# AMP_OP.net
KiCad netlist of a schematic drawn in EAGLE
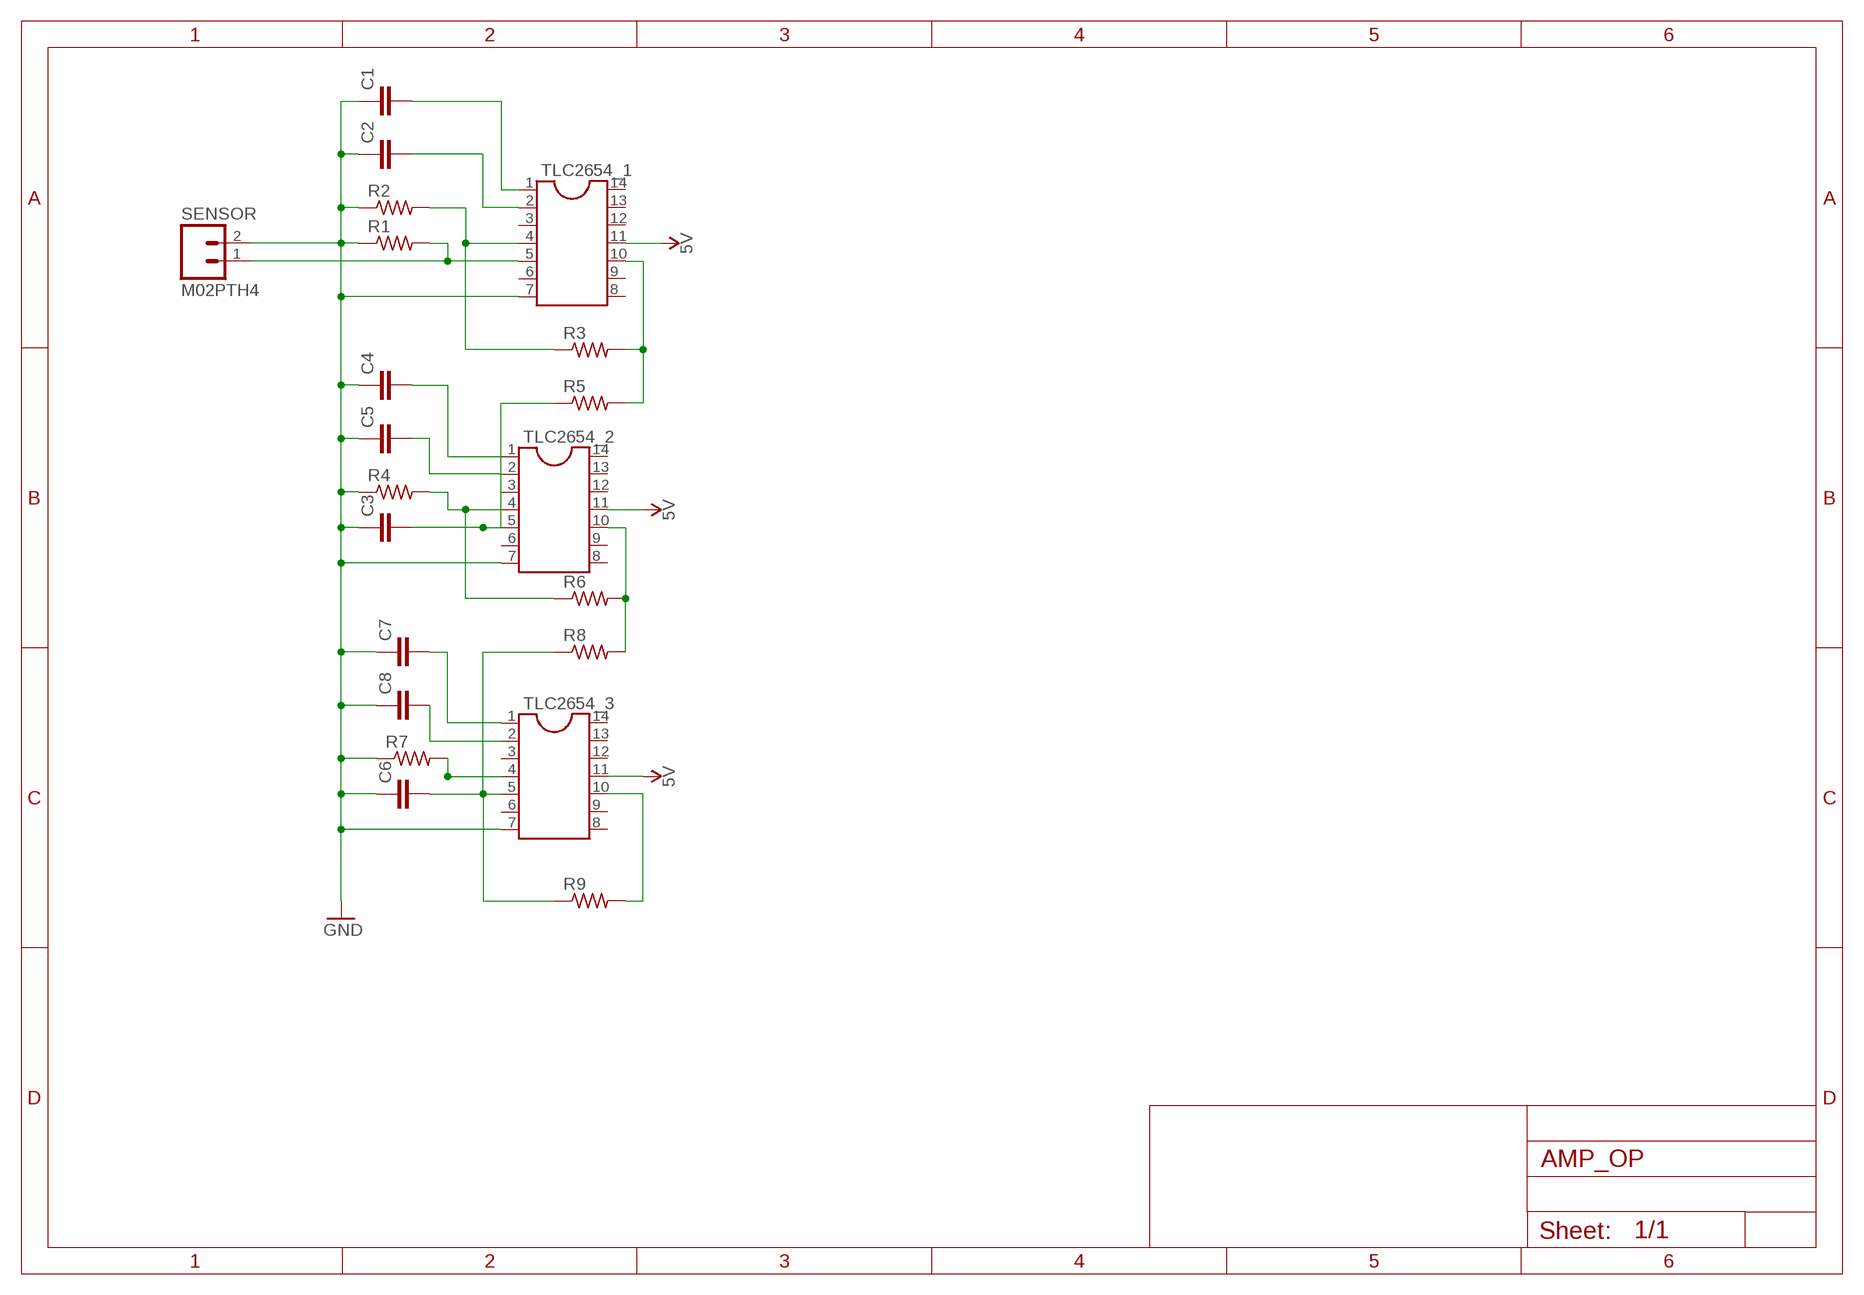
[diagram p0: schematic, sheet 1]

(export (version "E")
  (design (tool "Eeschema 10.0.6"))
  (components
    (comp (ref "C1")
      (value "C5/3.5")
      (footprint "eagle-import:C5B3.5")
      (libsource (lib "eagle-import") (part "C5/3.5"))
    )
    (comp (ref "C2")
      (value "C5/3.5")
      (footprint "eagle-import:C5B3.5")
      (libsource (lib "eagle-import") (part "C5/3.5"))
    )
    (comp (ref "C3")
      (value "C5/3.5")
      (footprint "eagle-import:C5B3.5")
      (libsource (lib "eagle-import") (part "C5/3.5"))
    )
    (comp (ref "C4")
      (value "C5/3.5")
      (footprint "eagle-import:C5B3.5")
      (libsource (lib "eagle-import") (part "C5/3.5"))
    )
    (comp (ref "C5")
      (value "C5/3.5")
      (footprint "eagle-import:C5B3.5")
      (libsource (lib "eagle-import") (part "C5/3.5"))
    )
    (comp (ref "C6")
      (value "C5/3.5")
      (footprint "eagle-import:C5B3.5")
      (libsource (lib "eagle-import") (part "C5/3.5"))
    )
    (comp (ref "C7")
      (value "C5/3.5")
      (footprint "eagle-import:C5B3.5")
      (libsource (lib "eagle-import") (part "C5/3.5"))
    )
    (comp (ref "C8")
      (value "C5/3.5")
      (footprint "eagle-import:C5B3.5")
      (libsource (lib "eagle-import") (part "C5/3.5"))
    )
    (comp (ref "R1")
      (value "R-US_0207/9")
      (footprint "eagle-import:0207_9")
      (libsource (lib "eagle-import") (part "R-US_0207/9"))
    )
    (comp (ref "R2")
      (value "R-US_0207/9")
      (footprint "eagle-import:0207_9")
      (libsource (lib "eagle-import") (part "R-US_0207/9"))
    )
    (comp (ref "R3")
      (value "R-US_0207/9")
      (footprint "eagle-import:0207_9")
      (libsource (lib "eagle-import") (part "R-US_0207/9"))
    )
    (comp (ref "R4")
      (value "R-US_0207/9")
      (footprint "eagle-import:0207_9")
      (libsource (lib "eagle-import") (part "R-US_0207/9"))
    )
    (comp (ref "R5")
      (value "R-US_0207/9")
      (footprint "eagle-import:0207_9")
      (libsource (lib "eagle-import") (part "R-US_0207/9"))
    )
    (comp (ref "R6")
      (value "R-US_0207/9")
      (footprint "eagle-import:0207_9")
      (libsource (lib "eagle-import") (part "R-US_0207/9"))
    )
    (comp (ref "R7")
      (value "R-US_0207/9")
      (footprint "eagle-import:0207_9")
      (libsource (lib "eagle-import") (part "R-US_0207/9"))
    )
    (comp (ref "R8")
      (value "R-US_0207/9")
      (footprint "eagle-import:0207_9")
      (libsource (lib "eagle-import") (part "R-US_0207/9"))
    )
    (comp (ref "R9")
      (value "R-US_0207/9")
      (footprint "eagle-import:0207_9")
      (libsource (lib "eagle-import") (part "R-US_0207/9"))
    )
    (comp (ref "SENSOR")
      (value "M02PTH4")
      (footprint "eagle-import:1X02_XTRA_BIG")
      (libsource (lib "eagle-import") (part "M02PTH4"))
    )
    (comp (ref "TLC2654_1")
      (value "DIL14")
      (footprint "eagle-import:DIL14")
      (libsource (lib "eagle-import") (part "DIL14"))
    )
    (comp (ref "TLC2654_2")
      (value "DIL14")
      (footprint "eagle-import:DIL14")
      (libsource (lib "eagle-import") (part "DIL14"))
    )
    (comp (ref "TLC2654_3")
      (value "DIL14")
      (footprint "eagle-import:DIL14")
      (libsource (lib "eagle-import") (part "DIL14"))
    )
  )
  (nets
    (net (code "1") (name "5V") (class "Default")
      (node (ref "TLC2654_1") (pin "11") (pinfunction "11_11") (pintype "passive"))
      (node (ref "TLC2654_2") (pin "11") (pinfunction "11_11") (pintype "passive"))
      (node (ref "TLC2654_3") (pin "11") (pinfunction "11_11") (pintype "passive"))
    )
    (net (code "2") (name "GND") (class "Default")
      (node (ref "C1") (pin "1") (pinfunction "1_1") (pintype "passive"))
      (node (ref "C2") (pin "1") (pinfunction "1_1") (pintype "passive"))
      (node (ref "C3") (pin "1") (pinfunction "1_1") (pintype "passive"))
      (node (ref "C4") (pin "1") (pinfunction "1_1") (pintype "passive"))
      (node (ref "C5") (pin "1") (pinfunction "1_1") (pintype "passive"))
      (node (ref "C6") (pin "1") (pinfunction "1_1") (pintype "passive"))
      (node (ref "C7") (pin "1") (pinfunction "1_1") (pintype "passive"))
      (node (ref "C8") (pin "1") (pinfunction "1_1") (pintype "passive"))
      (node (ref "R1") (pin "1") (pinfunction "1_1") (pintype "passive"))
      (node (ref "R2") (pin "1") (pinfunction "1_1") (pintype "passive"))
      (node (ref "R4") (pin "1") (pinfunction "1_1") (pintype "passive"))
      (node (ref "R7") (pin "1") (pinfunction "1_1") (pintype "passive"))
      (node (ref "SENSOR") (pin "2") (pinfunction "2_2") (pintype "passive"))
      (node (ref "TLC2654_1") (pin "7") (pinfunction "7_7") (pintype "passive"))
      (node (ref "TLC2654_2") (pin "7") (pinfunction "7_7") (pintype "passive"))
      (node (ref "TLC2654_3") (pin "7") (pinfunction "7_7") (pintype "passive"))
    )
    (net (code "3") (name "Net-(C1-Pad2)") (class "Default")
      (node (ref "C1") (pin "2") (pinfunction "2_2") (pintype "passive"))
      (node (ref "TLC2654_1") (pin "1") (pinfunction "1_1") (pintype "passive"))
    )
    (net (code "4") (name "Net-(C2-Pad2)") (class "Default")
      (node (ref "C2") (pin "2") (pinfunction "2_2") (pintype "passive"))
      (node (ref "TLC2654_1") (pin "2") (pinfunction "2_2") (pintype "passive"))
    )
    (net (code "5") (name "Net-(C3-Pad2)") (class "Default")
      (node (ref "C3") (pin "2") (pinfunction "2_2") (pintype "passive"))
      (node (ref "R5") (pin "1") (pinfunction "1_1") (pintype "passive"))
      (node (ref "TLC2654_2") (pin "5") (pinfunction "5_5") (pintype "passive"))
    )
    (net (code "6") (name "Net-(C4-Pad2)") (class "Default")
      (node (ref "C4") (pin "2") (pinfunction "2_2") (pintype "passive"))
      (node (ref "TLC2654_2") (pin "1") (pinfunction "1_1") (pintype "passive"))
    )
    (net (code "7") (name "Net-(C5-Pad2)") (class "Default")
      (node (ref "C5") (pin "2") (pinfunction "2_2") (pintype "passive"))
      (node (ref "TLC2654_2") (pin "2") (pinfunction "2_2") (pintype "passive"))
    )
    (net (code "8") (name "Net-(C6-Pad2)") (class "Default")
      (node (ref "C6") (pin "2") (pinfunction "2_2") (pintype "passive"))
      (node (ref "R8") (pin "1") (pinfunction "1_1") (pintype "passive"))
      (node (ref "R9") (pin "1") (pinfunction "1_1") (pintype "passive"))
      (node (ref "TLC2654_3") (pin "5") (pinfunction "5_5") (pintype "passive"))
    )
    (net (code "9") (name "Net-(C7-Pad2)") (class "Default")
      (node (ref "C7") (pin "2") (pinfunction "2_2") (pintype "passive"))
      (node (ref "TLC2654_3") (pin "1") (pinfunction "1_1") (pintype "passive"))
    )
    (net (code "10") (name "Net-(C8-Pad2)") (class "Default")
      (node (ref "C8") (pin "2") (pinfunction "2_2") (pintype "passive"))
      (node (ref "TLC2654_3") (pin "2") (pinfunction "2_2") (pintype "passive"))
    )
    (net (code "11") (name "Net-(R1-Pad2)") (class "Default")
      (node (ref "R1") (pin "2") (pinfunction "2_2") (pintype "passive"))
      (node (ref "SENSOR") (pin "1") (pinfunction "1_1") (pintype "passive"))
      (node (ref "TLC2654_1") (pin "5") (pinfunction "5_5") (pintype "passive"))
    )
    (net (code "12") (name "Net-(R2-Pad2)") (class "Default")
      (node (ref "R2") (pin "2") (pinfunction "2_2") (pintype "passive"))
      (node (ref "R3") (pin "1") (pinfunction "1_1") (pintype "passive"))
      (node (ref "TLC2654_1") (pin "4") (pinfunction "4_4") (pintype "passive"))
    )
    (net (code "13") (name "Net-(R3-Pad2)") (class "Default")
      (node (ref "R3") (pin "2") (pinfunction "2_2") (pintype "passive"))
      (node (ref "R5") (pin "2") (pinfunction "2_2") (pintype "passive"))
      (node (ref "TLC2654_1") (pin "10") (pinfunction "10_10") (pintype "passive"))
    )
    (net (code "14") (name "Net-(R4-Pad2)") (class "Default")
      (node (ref "R4") (pin "2") (pinfunction "2_2") (pintype "passive"))
      (node (ref "R6") (pin "1") (pinfunction "1_1") (pintype "passive"))
      (node (ref "TLC2654_2") (pin "4") (pinfunction "4_4") (pintype "passive"))
    )
    (net (code "15") (name "Net-(R6-Pad2)") (class "Default")
      (node (ref "R6") (pin "2") (pinfunction "2_2") (pintype "passive"))
      (node (ref "R8") (pin "2") (pinfunction "2_2") (pintype "passive"))
      (node (ref "TLC2654_2") (pin "10") (pinfunction "10_10") (pintype "passive"))
    )
    (net (code "16") (name "Net-(R7-Pad2)") (class "Default")
      (node (ref "R7") (pin "2") (pinfunction "2_2") (pintype "passive"))
      (node (ref "TLC2654_3") (pin "4") (pinfunction "4_4") (pintype "passive"))
    )
    (net (code "17") (name "Net-(R9-Pad2)") (class "Default")
      (node (ref "R9") (pin "2") (pinfunction "2_2") (pintype "passive"))
      (node (ref "TLC2654_3") (pin "10") (pinfunction "10_10") (pintype "passive"))
    )
    (net (code "18") (name "unconnected-(TLC2654_1-Pad3)") (class "Default")
      (node (ref "TLC2654_1") (pin "3") (pinfunction "3_3") (pintype "passive"))
    )
    (net (code "19") (name "unconnected-(TLC2654_1-Pad6)") (class "Default")
      (node (ref "TLC2654_1") (pin "6") (pinfunction "6_6") (pintype "passive"))
    )
    (net (code "20") (name "unconnected-(TLC2654_1-Pad8)") (class "Default")
      (node (ref "TLC2654_1") (pin "8") (pinfunction "8_8") (pintype "passive"))
    )
    (net (code "21") (name "unconnected-(TLC2654_1-Pad9)") (class "Default")
      (node (ref "TLC2654_1") (pin "9") (pinfunction "9_9") (pintype "passive"))
    )
    (net (code "22") (name "unconnected-(TLC2654_1-Pad12)") (class "Default")
      (node (ref "TLC2654_1") (pin "12") (pinfunction "12_12") (pintype "passive"))
    )
    (net (code "23") (name "unconnected-(TLC2654_1-Pad13)") (class "Default")
      (node (ref "TLC2654_1") (pin "13") (pinfunction "13_13") (pintype "passive"))
    )
    (net (code "24") (name "unconnected-(TLC2654_1-Pad14)") (class "Default")
      (node (ref "TLC2654_1") (pin "14") (pinfunction "14_14") (pintype "passive"))
    )
    (net (code "25") (name "unconnected-(TLC2654_2-Pad3)") (class "Default")
      (node (ref "TLC2654_2") (pin "3") (pinfunction "3_3") (pintype "passive"))
    )
    (net (code "26") (name "unconnected-(TLC2654_2-Pad6)") (class "Default")
      (node (ref "TLC2654_2") (pin "6") (pinfunction "6_6") (pintype "passive"))
    )
    (net (code "27") (name "unconnected-(TLC2654_2-Pad8)") (class "Default")
      (node (ref "TLC2654_2") (pin "8") (pinfunction "8_8") (pintype "passive"))
    )
    (net (code "28") (name "unconnected-(TLC2654_2-Pad9)") (class "Default")
      (node (ref "TLC2654_2") (pin "9") (pinfunction "9_9") (pintype "passive"))
    )
    (net (code "29") (name "unconnected-(TLC2654_2-Pad12)") (class "Default")
      (node (ref "TLC2654_2") (pin "12") (pinfunction "12_12") (pintype "passive"))
    )
    (net (code "30") (name "unconnected-(TLC2654_2-Pad13)") (class "Default")
      (node (ref "TLC2654_2") (pin "13") (pinfunction "13_13") (pintype "passive"))
    )
    (net (code "31") (name "unconnected-(TLC2654_2-Pad14)") (class "Default")
      (node (ref "TLC2654_2") (pin "14") (pinfunction "14_14") (pintype "passive"))
    )
    (net (code "32") (name "unconnected-(TLC2654_3-Pad3)") (class "Default")
      (node (ref "TLC2654_3") (pin "3") (pinfunction "3_3") (pintype "passive"))
    )
    (net (code "33") (name "unconnected-(TLC2654_3-Pad6)") (class "Default")
      (node (ref "TLC2654_3") (pin "6") (pinfunction "6_6") (pintype "passive"))
    )
    (net (code "34") (name "unconnected-(TLC2654_3-Pad8)") (class "Default")
      (node (ref "TLC2654_3") (pin "8") (pinfunction "8_8") (pintype "passive"))
    )
    (net (code "35") (name "unconnected-(TLC2654_3-Pad9)") (class "Default")
      (node (ref "TLC2654_3") (pin "9") (pinfunction "9_9") (pintype "passive"))
    )
    (net (code "36") (name "unconnected-(TLC2654_3-Pad12)") (class "Default")
      (node (ref "TLC2654_3") (pin "12") (pinfunction "12_12") (pintype "passive"))
    )
    (net (code "37") (name "unconnected-(TLC2654_3-Pad13)") (class "Default")
      (node (ref "TLC2654_3") (pin "13") (pinfunction "13_13") (pintype "passive"))
    )
    (net (code "38") (name "unconnected-(TLC2654_3-Pad14)") (class "Default")
      (node (ref "TLC2654_3") (pin "14") (pinfunction "14_14") (pintype "passive"))
    )
  )
)
